# Bigger_ParolaV1.net
KiCad netlist of a schematic drawn in EAGLE
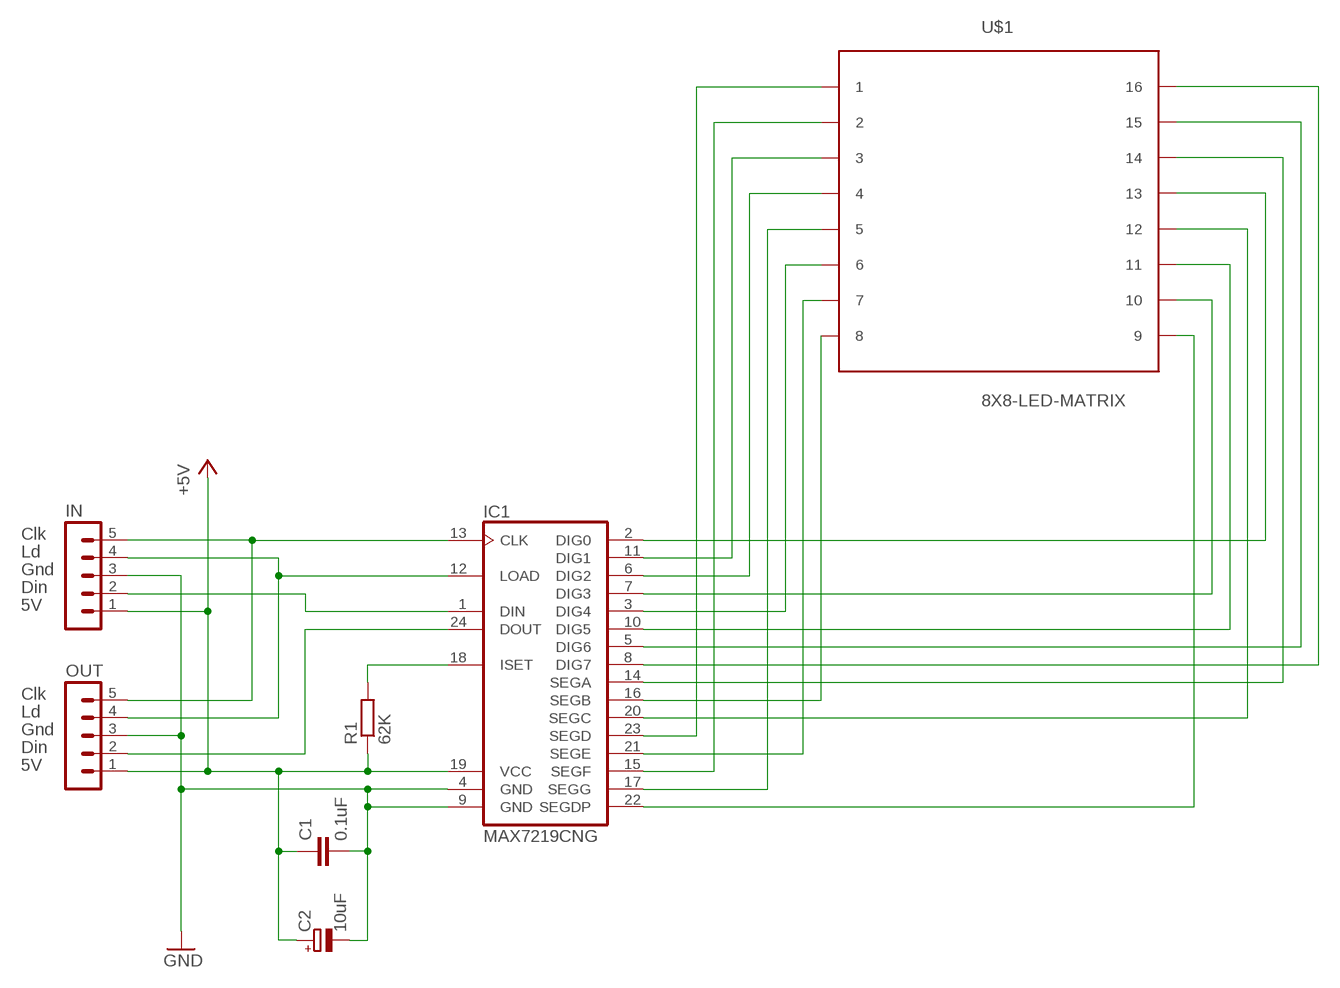
[diagram p0: schematic, sheet 1]

(export (version "E")
  (design (tool "Eeschema 10.0.6"))
  (components
    (comp (ref "C1")
      (value "0.1uF")
      (footprint "eagle-import:C025-024X044")
      (libsource (lib "eagle-import") (part "C-EU025-024X044"))
    )
    (comp (ref "C2")
      (value "10uF")
      (footprint "eagle-import:E2-5")
      (libsource (lib "eagle-import") (part "CPOL-EUE2-5"))
    )
    (comp (ref "IC1")
      (value "MAX7219CNG")
      (footprint "eagle-import:DIL24-3")
      (fields (field (name "MF") "MAXIM"))
      (libsource (lib "eagle-import") (part "MAX7219CNG"))
    )
    (comp (ref "IN")
      (value "MAR05-1")
      (footprint "eagle-import:MAR05-1")
      (libsource (lib "eagle-import") (part "MAR05-1"))
    )
    (comp (ref "OUT")
      (value "MAR05-1")
      (footprint "eagle-import:MAR05-1")
      (libsource (lib "eagle-import") (part "MAR05-1"))
    )
    (comp (ref "R1")
      (value "62K")
      (footprint "eagle-import:0207_10")
      (libsource (lib "eagle-import") (part "R-EU_0207/10"))
    )
    (comp (ref "U$1")
      (value "8X8-LED-MATRIX")
      (footprint "eagle-import:8X8-LED-MATRIX")
      (libsource (lib "eagle-import") (part "8X8-LED-MATRIX"))
    )
  )
  (nets
    (net (code "1") (name "+5V") (class "Default")
      (node (ref "C1") (pin "1") (pinfunction "1_1") (pintype "passive"))
      (node (ref "C2") (pin "+") (pinfunction "+_+") (pintype "passive"))
      (node (ref "IC1") (pin "19") (pinfunction "VCC_19") (pintype "power_in"))
      (node (ref "IN") (pin "1") (pinfunction "1_1") (pintype "passive"))
      (node (ref "OUT") (pin "1") (pinfunction "1_1") (pintype "passive"))
      (node (ref "R1") (pin "1") (pinfunction "1_1") (pintype "passive"))
    )
    (net (code "2") (name "GND") (class "Default")
      (node (ref "C1") (pin "2") (pinfunction "2_2") (pintype "passive"))
      (node (ref "C2") (pin "-") (pinfunction "-_-") (pintype "passive"))
      (node (ref "IC1") (pin "4") (pinfunction "GND_4") (pintype "power_in"))
      (node (ref "IC1") (pin "9") (pinfunction "GND_9") (pintype "power_in"))
      (node (ref "IN") (pin "3") (pinfunction "3_3") (pintype "passive"))
      (node (ref "OUT") (pin "3") (pinfunction "3_3") (pintype "passive"))
    )
    (net (code "3") (name "Net-(IC1-CLK)") (class "Default")
      (node (ref "IC1") (pin "13") (pinfunction "CLK_13") (pintype "input"))
      (node (ref "IN") (pin "5") (pinfunction "5_5") (pintype "passive"))
      (node (ref "OUT") (pin "5") (pinfunction "5_5") (pintype "passive"))
    )
    (net (code "4") (name "Net-(IC1-DIG0)") (class "Default")
      (node (ref "IC1") (pin "2") (pinfunction "DIG0_2") (pintype "output"))
      (node (ref "U$1") (pin "P$13") (pinfunction "13_P$13") (pintype "bidirectional"))
    )
    (net (code "5") (name "Net-(IC1-DIG1)") (class "Default")
      (node (ref "IC1") (pin "11") (pinfunction "DIG1_11") (pintype "output"))
      (node (ref "U$1") (pin "P$3") (pinfunction "3_P$3") (pintype "bidirectional"))
    )
    (net (code "6") (name "Net-(IC1-DIG2)") (class "Default")
      (node (ref "IC1") (pin "6") (pinfunction "DIG2_6") (pintype "output"))
      (node (ref "U$1") (pin "P$4") (pinfunction "4_P$4") (pintype "bidirectional"))
    )
    (net (code "7") (name "Net-(IC1-DIG3)") (class "Default")
      (node (ref "IC1") (pin "7") (pinfunction "DIG3_7") (pintype "output"))
      (node (ref "U$1") (pin "P$10") (pinfunction "10_P$10") (pintype "bidirectional"))
    )
    (net (code "8") (name "Net-(IC1-DIG4)") (class "Default")
      (node (ref "IC1") (pin "3") (pinfunction "DIG4_3") (pintype "output"))
      (node (ref "U$1") (pin "P$6") (pinfunction "6_P$6") (pintype "bidirectional"))
    )
    (net (code "9") (name "Net-(IC1-DIG5)") (class "Default")
      (node (ref "IC1") (pin "10") (pinfunction "DIG5_10") (pintype "output"))
      (node (ref "U$1") (pin "P$11") (pinfunction "11_P$11") (pintype "bidirectional"))
    )
    (net (code "10") (name "Net-(IC1-DIG6)") (class "Default")
      (node (ref "IC1") (pin "5") (pinfunction "DIG6_5") (pintype "output"))
      (node (ref "U$1") (pin "P$15") (pinfunction "15_P$15") (pintype "bidirectional"))
    )
    (net (code "11") (name "Net-(IC1-DIG7)") (class "Default")
      (node (ref "IC1") (pin "8") (pinfunction "DIG7_8") (pintype "output"))
      (node (ref "U$1") (pin "P$16") (pinfunction "16_P$16") (pintype "bidirectional"))
    )
    (net (code "12") (name "Net-(IC1-DIN)") (class "Default")
      (node (ref "IC1") (pin "1") (pinfunction "DIN_1") (pintype "input"))
      (node (ref "IN") (pin "2") (pinfunction "2_2") (pintype "passive"))
    )
    (net (code "13") (name "Net-(IC1-DOUT)") (class "Default")
      (node (ref "IC1") (pin "24") (pinfunction "DOUT_24") (pintype "output"))
      (node (ref "OUT") (pin "2") (pinfunction "2_2") (pintype "passive"))
    )
    (net (code "14") (name "Net-(IC1-ISET)") (class "Default")
      (node (ref "IC1") (pin "18") (pinfunction "ISET_18") (pintype "input"))
      (node (ref "R1") (pin "2") (pinfunction "2_2") (pintype "passive"))
    )
    (net (code "15") (name "Net-(IC1-LOAD)") (class "Default")
      (node (ref "IC1") (pin "12") (pinfunction "LOAD_12") (pintype "input"))
      (node (ref "IN") (pin "4") (pinfunction "4_4") (pintype "passive"))
      (node (ref "OUT") (pin "4") (pinfunction "4_4") (pintype "passive"))
    )
    (net (code "16") (name "Net-(IC1-SEGA)") (class "Default")
      (node (ref "IC1") (pin "14") (pinfunction "SEGA_14") (pintype "output"))
      (node (ref "U$1") (pin "P$14") (pinfunction "14_P$14") (pintype "bidirectional"))
    )
    (net (code "17") (name "Net-(IC1-SEGB)") (class "Default")
      (node (ref "IC1") (pin "16") (pinfunction "SEGB_16") (pintype "output"))
      (node (ref "U$1") (pin "P$8") (pinfunction "8_P$8") (pintype "bidirectional"))
    )
    (net (code "18") (name "Net-(IC1-SEGC)") (class "Default")
      (node (ref "IC1") (pin "20") (pinfunction "SEGC_20") (pintype "output"))
      (node (ref "U$1") (pin "P$12") (pinfunction "12_P$12") (pintype "bidirectional"))
    )
    (net (code "19") (name "Net-(IC1-SEGD)") (class "Default")
      (node (ref "IC1") (pin "23") (pinfunction "SEGD_23") (pintype "output"))
      (node (ref "U$1") (pin "P$1") (pinfunction "1_P$1") (pintype "bidirectional"))
    )
    (net (code "20") (name "Net-(IC1-SEGDP)") (class "Default")
      (node (ref "IC1") (pin "22") (pinfunction "SEGDP_22") (pintype "output"))
      (node (ref "U$1") (pin "P$9") (pinfunction "9_P$9") (pintype "bidirectional"))
    )
    (net (code "21") (name "Net-(IC1-SEGE)") (class "Default")
      (node (ref "IC1") (pin "21") (pinfunction "SEGE_21") (pintype "output"))
      (node (ref "U$1") (pin "P$7") (pinfunction "7_P$7") (pintype "bidirectional"))
    )
    (net (code "22") (name "Net-(IC1-SEGF)") (class "Default")
      (node (ref "IC1") (pin "15") (pinfunction "SEGF_15") (pintype "output"))
      (node (ref "U$1") (pin "P$2") (pinfunction "2_P$2") (pintype "bidirectional"))
    )
    (net (code "23") (name "Net-(IC1-SEGG)") (class "Default")
      (node (ref "IC1") (pin "17") (pinfunction "SEGG_17") (pintype "output"))
      (node (ref "U$1") (pin "P$5") (pinfunction "5_P$5") (pintype "bidirectional"))
    )
  )
)
